# radioslave.net
KiCad netlist of a schematic drawn in Altium Designer
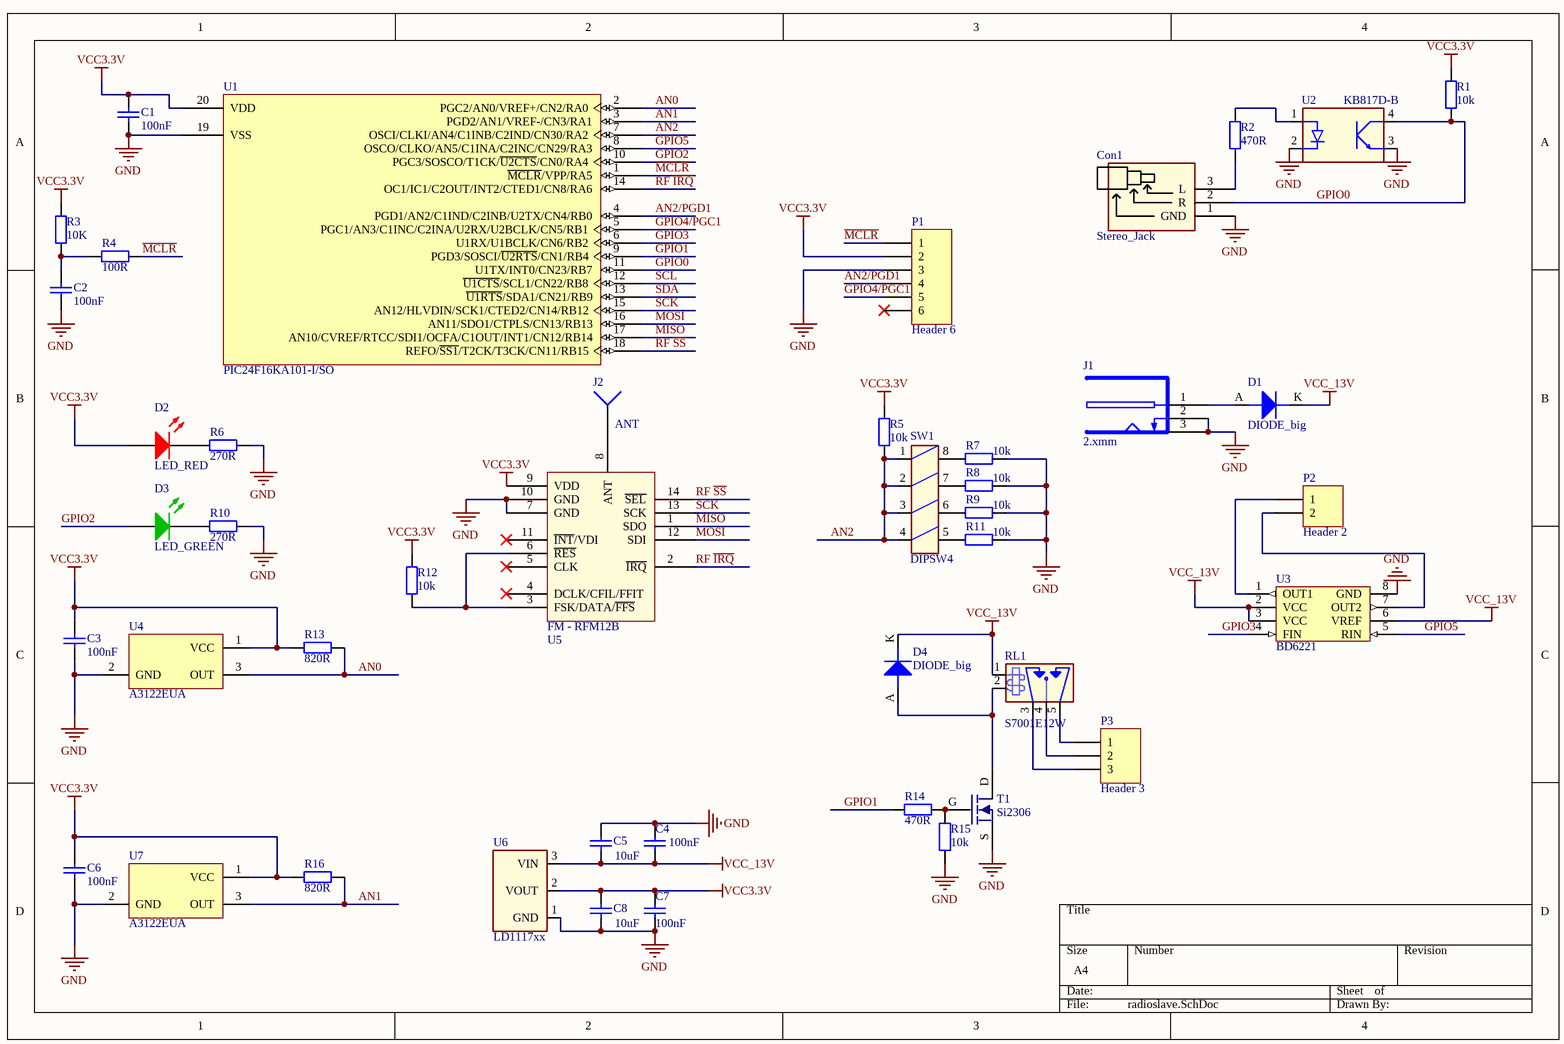
[diagram p0: radioslave.SchDoc]

(export (version "E")
  (design (tool "Eeschema 10.0.6"))
  (components
    (comp (ref "C1")
      (value "100nF")
      (footprint "FP_0805_CAP_060")
      (description "Capacitor")
      (fields (field (name "PUBLISHER") "Altium Limited"))
      (libsource (lib "Miscellaneous Devices") (part "Cap"))
    )
    (comp (ref "C2")
      (value "100nF")
      (footprint "FP_0805_CAP_060")
      (description "Capacitor")
      (fields (field (name "PUBLISHER") "Altium Limited"))
      (libsource (lib "Miscellaneous Devices") (part "Cap"))
    )
    (comp (ref "C3")
      (value "100nF")
      (footprint "FP_0805_CAP_060")
      (description "Capacitor")
      (fields (field (name "PUBLISHER") "Altium Limited"))
      (libsource (lib "Miscellaneous Devices") (part "Cap"))
    )
    (comp (ref "C4")
      (value "100nF")
      (footprint "FP_0603_CAP_080")
      (description "Capacitor")
      (fields (field (name "PUBLISHER") "Altium Limited"))
      (libsource (lib "Miscellaneous Devices") (part "Cap"))
    )
    (comp (ref "C5")
      (value "10uF")
      (footprint "FP_1206_CAP_085")
      (description "Capacitor")
      (fields (field (name "PUBLISHER") "Altium Limited"))
      (libsource (lib "Miscellaneous Devices") (part "Cap"))
    )
    (comp (ref "C6")
      (value "100nF")
      (footprint "FP_0805_CAP_060")
      (description "Capacitor")
      (fields (field (name "PUBLISHER") "Altium Limited"))
      (libsource (lib "Miscellaneous Devices") (part "Cap"))
    )
    (comp (ref "C7")
      (value "100nF")
      (footprint "FP_0603_CAP_080")
      (description "Capacitor")
      (fields (field (name "PUBLISHER") "Altium Limited"))
      (libsource (lib "Miscellaneous Devices") (part "Cap"))
    )
    (comp (ref "C8")
      (value "10uF")
      (footprint "FP_1206_CAP_085")
      (description "Capacitor")
      (fields (field (name "PUBLISHER") "Altium Limited"))
      (libsource (lib "Miscellaneous Devices") (part "Cap"))
    )
    (comp (ref "Con1")
      (value "Stereo_Jack")
      (footprint "STEREO_JACK")
      (libsource (lib "Connector") (part "Stereo_Jack"))
    )
    (comp (ref "D1")
      (value "DIODE_big")
      (footprint "FP_SMA DO214AC")
      (libsource (lib "Diode") (part "DIODE_big"))
    )
    (comp (ref "D2")
      (value "LED_RED")
      (footprint "FP_0805_LED_RED")
      (description "Typical LED")
      (libsource (lib "Led_optical") (part "LED_R"))
    )
    (comp (ref "D3")
      (value "LED_GREEN")
      (footprint "FP_0805_LED_RED")
      (description "Typical LED")
      (libsource (lib "Led_optical") (part "LED_G"))
    )
    (comp (ref "D4")
      (value "DIODE_big")
      (footprint "FP_SMA DO214AC")
      (libsource (lib "Diode") (part "DIODE_big"))
    )
    (comp (ref "J1")
      (value "2.xmm")
      (footprint "FP_DC_TAP_ANYA")
      (description "2.xmm DC HEBA25 TÁPFESZÜLTSÉG ALJZAT ZÁRT, NYÁKBA 90°")
      (libsource (lib "Connector") (part "DC_TAP_ANYA"))
    )
    (comp (ref "J2")
      (value "ANT")
      (footprint "PIN1")
      (description "Socket")
      (fields (field (name "PUBLISHER") "Altium Limited"))
      (libsource (lib "Miscellaneous Connectors") (part "Socket"))
    )
    (comp (ref "P1")
      (value "Header 6")
      (footprint "HDR1X6")
      (description "Header, 6-Pin")
      (fields (field (name "PUBLISHER") "Altium Limited"))
      (libsource (lib "Miscellaneous Connectors") (part "Header 6"))
    )
    (comp (ref "P2")
      (value "Header 2")
      (footprint "HDR1X2")
      (description "Header, 2-Pin")
      (fields (field (name "PUBLISHER") "Altium Limited"))
      (libsource (lib "Miscellaneous Connectors") (part "Header 2"))
    )
    (comp (ref "P3")
      (value "Header 3")
      (footprint "SORKAPOCS 3 P RM3.81")
      (description "Header, 3-Pin")
      (fields (field (name "PUBLISHER") "Altium Limited"))
      (libsource (lib "Miscellaneous Connectors") (part "Header 3"))
    )
    (comp (ref "R1")
      (value "10k")
      (footprint "FP_0805_RES")
      (description "Resistor")
      (fields (field (name "PUBLISHER") "Altium Limited"))
      (libsource (lib "") (part "Res3_2"))
    )
    (comp (ref "R2")
      (value "470R")
      (footprint "FP_0805_RES")
      (description "Resistor")
      (fields (field (name "PUBLISHER") "Altium Limited"))
      (libsource (lib "") (part "Res3_2"))
    )
    (comp (ref "R3")
      (value "10K")
      (footprint "FP_0805_RES")
      (description "Resistor")
      (fields (field (name "PUBLISHER") "Altium Limited"))
      (libsource (lib "") (part "Res3_2"))
    )
    (comp (ref "R4")
      (value "100R")
      (footprint "FP_0805_RES")
      (description "Resistor")
      (fields (field (name "PUBLISHER") "Altium Limited"))
      (libsource (lib "Miscellaneous Devices") (part "Res3"))
    )
    (comp (ref "R5")
      (value "10k")
      (footprint "FP_0805_RES")
      (description "Resistor")
      (fields (field (name "PUBLISHER") "Altium Limited"))
      (libsource (lib "") (part "Res3_2"))
    )
    (comp (ref "R6")
      (value "270R")
      (footprint "FP_0805_RES")
      (description "Resistor")
      (fields (field (name "PUBLISHER") "Altium Limited"))
      (libsource (lib "Miscellaneous Devices") (part "Res3"))
    )
    (comp (ref "R7")
      (value "10k")
      (footprint "FP_0805_RES")
      (description "Resistor")
      (fields (field (name "PUBLISHER") "Altium Limited"))
      (libsource (lib "Miscellaneous Devices") (part "Res3"))
    )
    (comp (ref "R8")
      (value "10k")
      (footprint "FP_0805_RES")
      (description "Resistor")
      (fields (field (name "PUBLISHER") "Altium Limited"))
      (libsource (lib "Miscellaneous Devices") (part "Res3"))
    )
    (comp (ref "R9")
      (value "10k")
      (footprint "FP_0805_RES")
      (description "Resistor")
      (fields (field (name "PUBLISHER") "Altium Limited"))
      (libsource (lib "Miscellaneous Devices") (part "Res3"))
    )
    (comp (ref "R10")
      (value "270R")
      (footprint "FP_0805_RES")
      (description "Resistor")
      (fields (field (name "PUBLISHER") "Altium Limited"))
      (libsource (lib "Miscellaneous Devices") (part "Res3"))
    )
    (comp (ref "R11")
      (value "10k")
      (footprint "FP_0805_RES")
      (description "Resistor")
      (fields (field (name "PUBLISHER") "Altium Limited"))
      (libsource (lib "Miscellaneous Devices") (part "Res3"))
    )
    (comp (ref "R12")
      (value "10k")
      (footprint "FP_0805_RES")
      (description "Resistor")
      (fields (field (name "PUBLISHER") "Altium Limited"))
      (libsource (lib "") (part "Res3_1"))
    )
    (comp (ref "R13")
      (value "820R")
      (footprint "FP_0805_RES")
      (description "Resistor")
      (fields (field (name "PUBLISHER") "Altium Limited"))
      (libsource (lib "Miscellaneous Devices") (part "Res3"))
    )
    (comp (ref "R14")
      (value "470R")
      (footprint "FP_0805_RES")
      (description "Resistor")
      (fields (field (name "PUBLISHER") "Altium Limited"))
      (libsource (lib "Miscellaneous Devices") (part "Res3"))
    )
    (comp (ref "R15")
      (value "10k")
      (footprint "FP_0805_RES")
      (description "Resistor")
      (fields (field (name "PUBLISHER") "Altium Limited"))
      (libsource (lib "") (part "Res3_1"))
    )
    (comp (ref "R16")
      (value "820R")
      (footprint "FP_0805_RES")
      (description "Resistor")
      (fields (field (name "PUBLISHER") "Altium Limited"))
      (libsource (lib "Miscellaneous Devices") (part "Res3"))
    )
    (comp (ref "RL1")
      (value "S7001E12W")
      (footprint "RELAY_MORSE")
      (description "S7001E12W  12V morse 230AC/10A")
      (libsource (lib "Switch") (part "RELAY_MORSE"))
    )
    (comp (ref "SW1")
      (value "DIPSW4")
      (footprint "DIP switch 4 TH")
      (libsource (lib "Switch") (part "DIPSW4"))
    )
    (comp (ref "T1") (value "Si2306") (footprint "FET_SOT23") (libsource (lib "FET") (part "NMOS")))
    (comp (ref "U1")
      (value "PIC24F16KA101-I/SO")
      (footprint "SOIC-SO20_N")
      (fields (field (name "PUBLISHER") "Altium Limited"))
      (libsource (lib "Microchip Microcontroller 16-Bit PIC24F") (part "PIC24F16KA101-I/SO"))
    )
    (comp (ref "U2")
      (value "KB817D-B")
      (footprint "SOP-4")
      (description "KB817D-B (KIN) SOP-4L OPTOCOUPLER TRANS-OUT 300-600% 5kV SOP-4L [84-00-48]")
      (libsource (lib "Led_optical") (part "KB817D-B"))
    )
    (comp (ref "U3")
      (value "BD6221")
      (footprint "Digital:DIGITAL_SOIC8")
      (description "H_bridge")
      (libsource (lib "Digital") (part "BD6221"))
    )
    (comp (ref "U4")
      (value "A3122EUA")
      (footprint "Allegro_hall sensor")
      (description "Hall-Effect Switch for High-Temperature Operation")
      (fields (field (name "PUBLISHER") "Altium Limited"))
      (libsource (lib "Sensor") (part "A3122EUA"))
    )
    (comp (ref "U5")
      (value "RFM12B")
      (footprint "RFM12B-S1")
      (description "FM Module")
      (libsource (lib "EtherIOv2") (part "RFM12B"))
    )
    (comp (ref "U6")
      (value "LD1117xx")
      (footprint "SUPPLY_SOT223")
      (description "LD1117xx 3,3V lin reg")
      (libsource (lib "Supply") (part "LD1117xx"))
    )
    (comp (ref "U7")
      (value "A3122EUA")
      (footprint "Allegro_hall sensor")
      (description "Hall-Effect Switch for High-Temperature Operation")
      (fields (field (name "PUBLISHER") "Altium Limited"))
      (libsource (lib "Sensor") (part "A3122EUA"))
    )
  )
  (nets
    (net (code "1") (name "/AN0") (class "Default")
      (node (ref "R13") (pin "1") (pinfunction "1_1") (pintype "passive"))
      (node (ref "U1") (pin "2") (pinfunction "PGC2/AN0/VREF+/CN2/RA0_2") (pintype "bidirectional"))
      (node (ref "U4") (pin "3") (pinfunction "OUT_3") (pintype "open_collector"))
    )
    (net (code "2") (name "/AN1") (class "Default")
      (node (ref "R16") (pin "1") (pinfunction "1_1") (pintype "passive"))
      (node (ref "U1") (pin "3") (pinfunction "PGD2/AN1/VREF-/CN3/RA1_3") (pintype "bidirectional"))
      (node (ref "U7") (pin "3") (pinfunction "OUT_3") (pintype "open_collector"))
    )
    (net (code "3") (name "/AN2") (class "Default")
      (node (ref "R5") (pin "2") (pinfunction "2_2") (pintype "passive"))
      (node (ref "SW1") (pin "1") (pinfunction "1_1") (pintype "passive"))
      (node (ref "SW1") (pin "2") (pinfunction "2_2") (pintype "passive"))
      (node (ref "SW1") (pin "3") (pinfunction "3_3") (pintype "passive"))
      (node (ref "SW1") (pin "4") (pinfunction "4_4") (pintype "passive"))
      (node (ref "U1") (pin "7") (pinfunction "OSCI/CLKI/AN4/C1INB/C2IND/CN30/RA2_7") (pintype "bidirectional"))
    )
    (net (code "4") (name "/AN2{slash}PGD1") (class "Default")
      (node (ref "P1") (pin "4") (pinfunction "4_4") (pintype "passive"))
      (node (ref "U1") (pin "4") (pinfunction "PGD1/AN2/C1IND/C2INB/U2TX/CN4/RB0_4") (pintype "bidirectional"))
    )
    (net (code "5") (name "/GPIO0") (class "Default")
      (node (ref "Con1") (pin "2") (pinfunction "R_2") (pintype "passive"))
      (node (ref "R1") (pin "2") (pinfunction "2_2") (pintype "passive"))
      (node (ref "U1") (pin "11") (pinfunction "U1TX/INT0/CN23/RB7_11") (pintype "bidirectional"))
      (node (ref "U2") (pin "4") (pinfunction "C_4") (pintype "passive"))
    )
    (net (code "6") (name "/GPIO1") (class "Default")
      (node (ref "R14") (pin "2") (pinfunction "2_2") (pintype "passive"))
      (node (ref "U1") (pin "9") (pinfunction "PGD3/SOSCI/~{U2RTS}/CN1/RB4_9") (pintype "bidirectional"))
    )
    (net (code "7") (name "/GPIO2") (class "Default")
      (node (ref "D3") (pin "A") (pinfunction "A_A") (pintype "passive"))
      (node (ref "U1") (pin "10") (pinfunction "PGC3/SOSCO/T1CK/~{U2CTS}/CN0/RA4_10") (pintype "bidirectional"))
    )
    (net (code "8") (name "/GPIO3") (class "Default")
      (node (ref "U1") (pin "6") (pinfunction "U1RX/U1BCLK/CN6/RB2_6") (pintype "bidirectional"))
      (node (ref "U3") (pin "4") (pinfunction "FIN_4") (pintype "input"))
    )
    (net (code "9") (name "/GPIO4{slash}PGC1") (class "Default")
      (node (ref "P1") (pin "5") (pinfunction "5_5") (pintype "passive"))
      (node (ref "U1") (pin "5") (pinfunction "PGC1/AN3/C1INC/C2INA/U2RX/U2BCLK/CN5/RB1_5") (pintype "bidirectional"))
    )
    (net (code "10") (name "/GPIO5") (class "Default")
      (node (ref "U1") (pin "8") (pinfunction "OSCO/CLKO/AN5/C1INA/C2INC/CN29/RA3_8") (pintype "bidirectional"))
      (node (ref "U3") (pin "5") (pinfunction "RIN_5") (pintype "input"))
    )
    (net (code "11") (name "/MISO") (class "Default")
      (node (ref "U1") (pin "17") (pinfunction "AN10/CVREF/RTCC/SDI1/OCFA/C1OUT/INT1/CN12/RB14_17") (pintype "bidirectional"))
      (node (ref "U5") (pin "1") (pinfunction "SDO_1") (pintype "passive"))
    )
    (net (code "12") (name "/MOSI") (class "Default")
      (node (ref "U1") (pin "16") (pinfunction "AN11/SDO1/CTPLS/CN13/RB13_16") (pintype "bidirectional"))
      (node (ref "U5") (pin "12") (pinfunction "SDI_12") (pintype "passive"))
    )
    (net (code "13") (name "/RF ~{IRQ}") (class "Default")
      (node (ref "U1") (pin "14") (pinfunction "OC1/IC1/C2OUT/INT2/CTED1/CN8/RA6_14") (pintype "bidirectional"))
      (node (ref "U5") (pin "2") (pinfunction "~{IRQ}_2") (pintype "passive"))
    )
    (net (code "14") (name "/RF ~{SS}") (class "Default")
      (node (ref "U1") (pin "18") (pinfunction "REFO/~{SS1}/T2CK/T3CK/CN11/RB15_18") (pintype "bidirectional"))
      (node (ref "U5") (pin "14") (pinfunction "~{SEL}_14") (pintype "passive"))
    )
    (net (code "15") (name "/SCK") (class "Default")
      (node (ref "U1") (pin "15") (pinfunction "AN12/HLVDIN/SCK1/CTED2/CN14/RB12_15") (pintype "bidirectional"))
      (node (ref "U5") (pin "13") (pinfunction "SCK_13") (pintype "passive"))
    )
    (net (code "16") (name "/SCL") (class "Default")
      (node (ref "U1") (pin "12") (pinfunction "~{U1CTS}/SCL1/CN22/RB8_12") (pintype "bidirectional"))
    )
    (net (code "17") (name "/SDA") (class "Default")
      (node (ref "U1") (pin "13") (pinfunction "~{U1RTS}/SDA1/CN21/RB9_13") (pintype "bidirectional"))
    )
    (net (code "18") (name "/~{MCLR}") (class "Default")
      (node (ref "P1") (pin "1") (pinfunction "1_1") (pintype "passive"))
      (node (ref "R4") (pin "1") (pinfunction "1_1") (pintype "passive"))
      (node (ref "U1") (pin "1") (pinfunction "~{MCLR}/VPP/RA5_1") (pintype "bidirectional"))
    )
    (net (code "19") (name "GND") (class "Default")
      (node (ref "C1") (pin "1") (pinfunction "1_1") (pintype "passive"))
      (node (ref "C2") (pin "1") (pinfunction "1_1") (pintype "passive"))
      (node (ref "C3") (pin "1") (pinfunction "1_1") (pintype "passive"))
      (node (ref "C4") (pin "1") (pinfunction "1_1") (pintype "passive"))
      (node (ref "C5") (pin "2") (pinfunction "2_2") (pintype "passive"))
      (node (ref "C6") (pin "1") (pinfunction "1_1") (pintype "passive"))
      (node (ref "C7") (pin "2") (pinfunction "2_2") (pintype "passive"))
      (node (ref "C8") (pin "1") (pinfunction "1_1") (pintype "passive"))
      (node (ref "Con1") (pin "1") (pinfunction "GND_1") (pintype "passive"))
      (node (ref "J1") (pin "2") (pinfunction "GND_2") (pintype "power_in"))
      (node (ref "J1") (pin "3") (pinfunction "GND_3") (pintype "power_in"))
      (node (ref "P1") (pin "3") (pinfunction "3_3") (pintype "passive"))
      (node (ref "R10") (pin "1") (pinfunction "1_1") (pintype "passive"))
      (node (ref "R11") (pin "1") (pinfunction "1_1") (pintype "passive"))
      (node (ref "R15") (pin "1") (pinfunction "1_1") (pintype "passive"))
      (node (ref "R6") (pin "1") (pinfunction "1_1") (pintype "passive"))
      (node (ref "R7") (pin "1") (pinfunction "1_1") (pintype "passive"))
      (node (ref "R8") (pin "1") (pinfunction "1_1") (pintype "passive"))
      (node (ref "R9") (pin "1") (pinfunction "1_1") (pintype "passive"))
      (node (ref "T1") (pin "S") (pinfunction "S_S") (pintype "passive"))
      (node (ref "U1") (pin "19") (pinfunction "VSS_19") (pintype "power_in"))
      (node (ref "U2") (pin "2") (pinfunction "K_2") (pintype "passive"))
      (node (ref "U2") (pin "3") (pinfunction "E_3") (pintype "passive"))
      (node (ref "U3") (pin "8") (pinfunction "GND_8") (pintype "passive"))
      (node (ref "U4") (pin "2") (pinfunction "GND_2") (pintype "power_in"))
      (node (ref "U5") (pin "10") (pinfunction "GND_10") (pintype "passive"))
      (node (ref "U5") (pin "7") (pinfunction "GND_7") (pintype "passive"))
      (node (ref "U6") (pin "1") (pinfunction "GND_1") (pintype "passive"))
      (node (ref "U7") (pin "2") (pinfunction "GND_2") (pintype "power_in"))
    )
    (net (code "20") (name "Net-(C2-Pad2)") (class "Default")
      (node (ref "C2") (pin "2") (pinfunction "2_2") (pintype "passive"))
      (node (ref "R3") (pin "2") (pinfunction "2_2") (pintype "passive"))
      (node (ref "R4") (pin "2") (pinfunction "2_2") (pintype "passive"))
    )
    (net (code "21") (name "Net-(Con1-L)") (class "Default")
      (node (ref "Con1") (pin "3") (pinfunction "L_3") (pintype "passive"))
      (node (ref "R2") (pin "2") (pinfunction "2_2") (pintype "passive"))
    )
    (net (code "22") (name "Net-(D2-PadK)") (class "Default")
      (node (ref "D2") (pin "K") (pinfunction "K_K") (pintype "passive"))
      (node (ref "R6") (pin "2") (pinfunction "2_2") (pintype "passive"))
    )
    (net (code "23") (name "Net-(D3-PadK)") (class "Default")
      (node (ref "D3") (pin "K") (pinfunction "K_K") (pintype "passive"))
      (node (ref "R10") (pin "2") (pinfunction "2_2") (pintype "passive"))
    )
    (net (code "24") (name "Net-(J1-9V)") (class "Default")
      (node (ref "D1") (pin "A") (pinfunction "A_A") (pintype "passive"))
      (node (ref "J1") (pin "1") (pinfunction "9V_1") (pintype "power_in"))
    )
    (net (code "25") (name "Net-(R7-Pad2)") (class "Default")
      (node (ref "R7") (pin "2") (pinfunction "2_2") (pintype "passive"))
      (node (ref "SW1") (pin "8") (pinfunction "8_8") (pintype "passive"))
    )
    (net (code "26") (name "Net-(R8-Pad2)") (class "Default")
      (node (ref "R8") (pin "2") (pinfunction "2_2") (pintype "passive"))
      (node (ref "SW1") (pin "7") (pinfunction "7_7") (pintype "passive"))
    )
    (net (code "27") (name "Net-(R9-Pad2)") (class "Default")
      (node (ref "R9") (pin "2") (pinfunction "2_2") (pintype "passive"))
      (node (ref "SW1") (pin "6") (pinfunction "6_6") (pintype "passive"))
    )
    (net (code "28") (name "Net-(R11-Pad2)") (class "Default")
      (node (ref "R11") (pin "2") (pinfunction "2_2") (pintype "passive"))
      (node (ref "SW1") (pin "5") (pinfunction "5_5") (pintype "passive"))
    )
    (net (code "29") (name "Net-(R14-Pad1)") (class "Default")
      (node (ref "R14") (pin "1") (pinfunction "1_1") (pintype "passive"))
      (node (ref "R15") (pin "2") (pinfunction "2_2") (pintype "passive"))
      (node (ref "T1") (pin "G") (pinfunction "G_G") (pintype "passive"))
    )
    (net (code "30") (name "Net-(RL1-COIL2+)") (class "Default")
      (node (ref "D4") (pin "A") (pinfunction "A_A") (pintype "passive"))
      (node (ref "RL1") (pin "2") (pinfunction "COIL2+_2") (pintype "passive"))
      (node (ref "T1") (pin "D") (pinfunction "D_D") (pintype "passive"))
    )
    (net (code "31") (name "Net-(RL1-COMMON)") (class "Default")
      (node (ref "P3") (pin "2") (pinfunction "2_2") (pintype "passive"))
      (node (ref "RL1") (pin "4") (pinfunction "COMMON_4") (pintype "passive"))
    )
    (net (code "32") (name "Net-(RL1-NC)") (class "Default")
      (node (ref "P3") (pin "3") (pinfunction "3_3") (pintype "passive"))
      (node (ref "RL1") (pin "3") (pinfunction "NC_3") (pintype "passive"))
    )
    (net (code "33") (name "Net-(RL1-NO)") (class "Default")
      (node (ref "P3") (pin "1") (pinfunction "1_1") (pintype "passive"))
      (node (ref "RL1") (pin "5") (pinfunction "NO_5") (pintype "passive"))
    )
    (net (code "34") (name "Net-(U2-A)") (class "Default")
      (node (ref "R2") (pin "1") (pinfunction "1_1") (pintype "passive"))
      (node (ref "U2") (pin "1") (pinfunction "A_1") (pintype "passive"))
    )
    (net (code "35") (name "Net-(U3-OUT1)") (class "Default")
      (node (ref "P2") (pin "1") (pinfunction "1_1") (pintype "passive"))
      (node (ref "U3") (pin "1") (pinfunction "OUT1_1") (pintype "output"))
    )
    (net (code "36") (name "Net-(U3-OUT2)") (class "Default")
      (node (ref "P2") (pin "2") (pinfunction "2_2") (pintype "passive"))
      (node (ref "U3") (pin "7") (pinfunction "OUT2_7") (pintype "output"))
    )
    (net (code "37") (name "Net-(U5-ANT)") (class "Default")
      (node (ref "J2") (pin "1") (pinfunction "1_1") (pintype "passive"))
      (node (ref "U5") (pin "8") (pinfunction "ANT_8") (pintype "passive"))
    )
    (net (code "38") (name "Net-(U5-FSK{slash}DATA{slash}~{FFS})") (class "Default")
      (node (ref "R12") (pin "1") (pinfunction "1_1") (pintype "passive"))
      (node (ref "U5") (pin "3") (pinfunction "FSK/DATA/~{FFS}_3") (pintype "passive"))
      (node (ref "U5") (pin "6") (pinfunction "~{RES}_6") (pintype "passive"))
    )
    (net (code "39") (name "VCC3.3V") (class "Default")
      (node (ref "C1") (pin "2") (pinfunction "2_2") (pintype "passive"))
      (node (ref "C3") (pin "2") (pinfunction "2_2") (pintype "passive"))
      (node (ref "C6") (pin "2") (pinfunction "2_2") (pintype "passive"))
      (node (ref "C7") (pin "1") (pinfunction "1_1") (pintype "passive"))
      (node (ref "C8") (pin "2") (pinfunction "2_2") (pintype "passive"))
      (node (ref "D2") (pin "A") (pinfunction "A_A") (pintype "passive"))
      (node (ref "P1") (pin "2") (pinfunction "2_2") (pintype "passive"))
      (node (ref "R1") (pin "1") (pinfunction "1_1") (pintype "passive"))
      (node (ref "R12") (pin "2") (pinfunction "2_2") (pintype "passive"))
      (node (ref "R13") (pin "2") (pinfunction "2_2") (pintype "passive"))
      (node (ref "R16") (pin "2") (pinfunction "2_2") (pintype "passive"))
      (node (ref "R3") (pin "1") (pinfunction "1_1") (pintype "passive"))
      (node (ref "R5") (pin "1") (pinfunction "1_1") (pintype "passive"))
      (node (ref "U1") (pin "20") (pinfunction "VDD_20") (pintype "power_in"))
      (node (ref "U4") (pin "1") (pinfunction "VCC_1") (pintype "power_in"))
      (node (ref "U5") (pin "9") (pinfunction "VDD_9") (pintype "passive"))
      (node (ref "U6") (pin "2") (pinfunction "VOUT_2") (pintype "passive"))
      (node (ref "U7") (pin "1") (pinfunction "VCC_1") (pintype "power_in"))
    )
    (net (code "40") (name "VCC_13V") (class "Default")
      (node (ref "C4") (pin "2") (pinfunction "2_2") (pintype "passive"))
      (node (ref "C5") (pin "1") (pinfunction "1_1") (pintype "passive"))
      (node (ref "D1") (pin "K") (pinfunction "K_K") (pintype "passive"))
      (node (ref "D4") (pin "K") (pinfunction "K_K") (pintype "passive"))
      (node (ref "RL1") (pin "1") (pinfunction "COIL1-_1") (pintype "passive"))
      (node (ref "U3") (pin "2") (pinfunction "VCC_2") (pintype "power_in"))
      (node (ref "U3") (pin "3") (pinfunction "VCC_3") (pintype "power_in"))
      (node (ref "U3") (pin "6") (pinfunction "VREF_6") (pintype "passive"))
      (node (ref "U6") (pin "3") (pinfunction "VIN_3") (pintype "passive"))
    )
    (net (code "41") (name "unconnected-(P1-Pad6)") (class "Default")
      (node (ref "P1") (pin "6") (pinfunction "6_6") (pintype "passive+no_connect"))
    )
    (net (code "42") (name "unconnected-(U5-CLK-Pad5)") (class "Default")
      (node (ref "U5") (pin "5") (pinfunction "CLK_5") (pintype "passive+no_connect"))
    )
    (net (code "43") (name "unconnected-(U5-DCLK{slash}CFIL{slash}FFIT-Pad4)") (class "Default")
      (node (ref "U5") (pin "4") (pinfunction "DCLK/CFIL/FFIT_4") (pintype "passive+no_connect"))
    )
    (net (code "44") (name "unconnected-(U5-~{INT}{slash}VDI-Pad11)") (class "Default")
      (node (ref "U5") (pin "11") (pinfunction "~{INT}/VDI_11") (pintype "passive+no_connect"))
    )
  )
)
